# SCH_Szachy-schemat_2025-07-13.net
KiCad netlist of a schematic drawn in EasyEDA
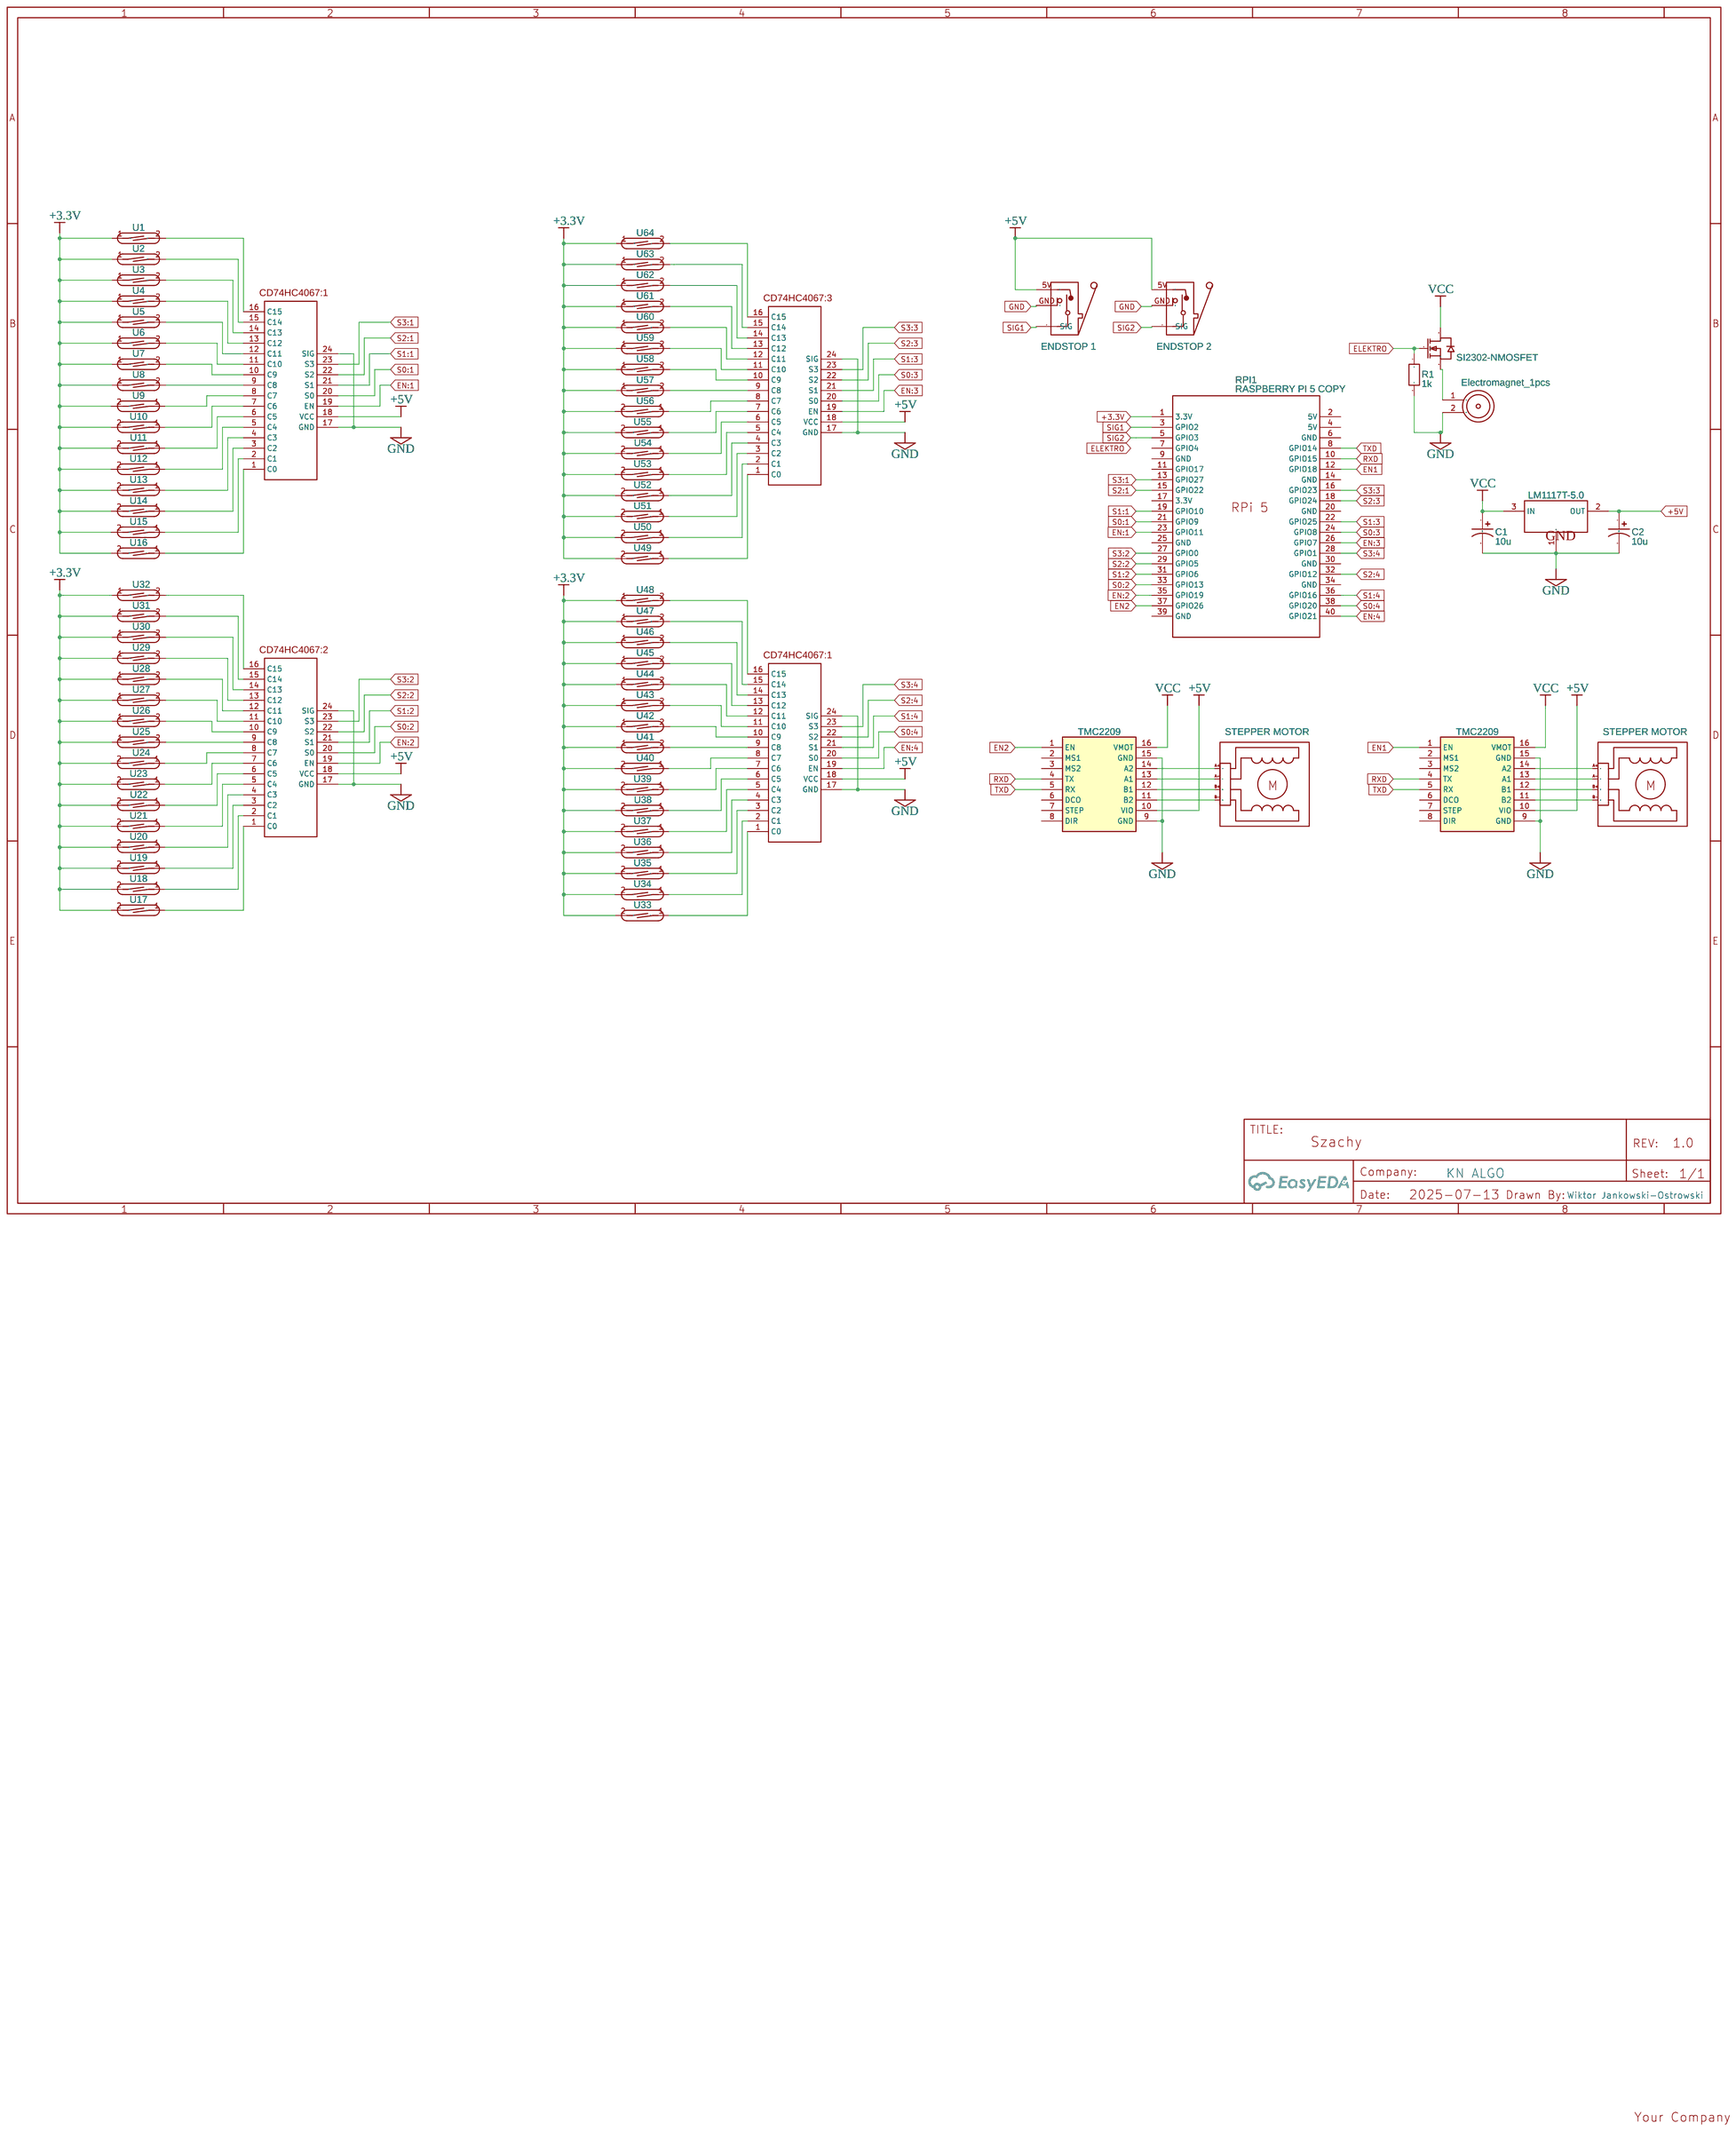
[diagram p0: schematic sheet]

(export (version "E")
  (design (tool "Eeschema 10.0.6"))
  (components
    (comp (ref "C1") (value "10u") (libsource (lib "") (part "C_Tan_SMD_A_US")))
    (comp (ref "C2") (value "10u") (libsource (lib "") (part "C_Tan_SMD_A_US")))
    (comp (ref "ESTP_FU1") (value "ENDSTOP 1") (libsource (lib "") (part "EndStop")))
    (comp (ref "ESTP_FU2") (value "ENDSTOP 2") (libsource (lib "") (part "EndStop")))
    (comp (ref "P1") (value "CD74HC4067SOLOV") (libsource (lib "") (part "CD74HC4067SOLOV")))
    (comp (ref "P2") (value "CD74HC4067SOLOV") (libsource (lib "") (part "CD74HC4067SOLOV_2")))
    (comp (ref "P3") (value "CD74HC4067SOLOV") (libsource (lib "") (part "CD74HC4067SOLOV")))
    (comp (ref "P4") (value "CD74HC4067SOLOV") (libsource (lib "") (part "CD74HC4067SOLOV_1")))
    (comp (ref "P5")
      (value "STEPPER MOTOR")
      (fields
        (field (name "Manufacturer Part") "Header-Male-2.54_1x6")
        (field (name "Manufacturer") "BOOMELE")
      )
      (libsource (lib "") (part "STEPPER MOTOR AM34HD1404-06 COPY"))
    )
    (comp (ref "P6")
      (value "STEPPER MOTOR")
      (fields
        (field (name "Manufacturer Part") "Header-Male-2.54_1x6")
        (field (name "Manufacturer") "BOOMELE")
      )
      (libsource (lib "") (part "STEPPER MOTOR AM34HD1404-06 COPY"))
    )
    (comp (ref "R1") (value "1k") (libsource (lib "") (part "R_0603_EU")))
    (comp (ref "RPI1")
      (value "RASPBERRY PI 5 COPY")
      (fields (field (name "Manufacturer") "Raspberry Pi 5 4GB"))
      (libsource (lib "") (part "RASPBERRY PI 5 COPY"))
    )
    (comp (ref "U1") (value "REED_SWITCH_D-C37") (libsource (lib "") (part "REED_SWITCH_D-C37")))
    (comp (ref "U2") (value "REED_SWITCH_D-C37") (libsource (lib "") (part "REED_SWITCH_D-C37")))
    (comp (ref "U3") (value "REED_SWITCH_D-C37") (libsource (lib "") (part "REED_SWITCH_D-C37")))
    (comp (ref "U4") (value "REED_SWITCH_D-C37") (libsource (lib "") (part "REED_SWITCH_D-C37")))
    (comp (ref "U5") (value "REED_SWITCH_D-C37") (libsource (lib "") (part "REED_SWITCH_D-C37")))
    (comp (ref "U6") (value "REED_SWITCH_D-C37") (libsource (lib "") (part "REED_SWITCH_D-C37")))
    (comp (ref "U7") (value "REED_SWITCH_D-C37") (libsource (lib "") (part "REED_SWITCH_D-C37")))
    (comp (ref "U8") (value "REED_SWITCH_D-C37") (libsource (lib "") (part "REED_SWITCH_D-C37")))
    (comp (ref "U9") (value "REED_SWITCH_D-C37") (libsource (lib "") (part "REED_SWITCH_D-C37_1")))
    (comp (ref "U10") (value "REED_SWITCH_D-C37") (libsource (lib "") (part "REED_SWITCH_D-C37_1")))
    (comp (ref "U11") (value "REED_SWITCH_D-C37") (libsource (lib "") (part "REED_SWITCH_D-C37_1")))
    (comp (ref "U12") (value "REED_SWITCH_D-C37") (libsource (lib "") (part "REED_SWITCH_D-C37_1")))
    (comp (ref "U13") (value "REED_SWITCH_D-C37") (libsource (lib "") (part "REED_SWITCH_D-C37_1")))
    (comp (ref "U14") (value "REED_SWITCH_D-C37") (libsource (lib "") (part "REED_SWITCH_D-C37_1")))
    (comp (ref "U15") (value "REED_SWITCH_D-C37") (libsource (lib "") (part "REED_SWITCH_D-C37_1")))
    (comp (ref "U16") (value "REED_SWITCH_D-C37") (libsource (lib "") (part "REED_SWITCH_D-C37_1")))
    (comp (ref "U17") (value "REED_SWITCH_D-C37") (libsource (lib "") (part "REED_SWITCH_D-C37_1")))
    (comp (ref "U18") (value "REED_SWITCH_D-C37") (libsource (lib "") (part "REED_SWITCH_D-C37_1")))
    (comp (ref "U19") (value "REED_SWITCH_D-C37") (libsource (lib "") (part "REED_SWITCH_D-C37_1")))
    (comp (ref "U20") (value "REED_SWITCH_D-C37") (libsource (lib "") (part "REED_SWITCH_D-C37_1")))
    (comp (ref "U21") (value "REED_SWITCH_D-C37") (libsource (lib "") (part "REED_SWITCH_D-C37_1")))
    (comp (ref "U22") (value "REED_SWITCH_D-C37") (libsource (lib "") (part "REED_SWITCH_D-C37_1")))
    (comp (ref "U23") (value "REED_SWITCH_D-C37") (libsource (lib "") (part "REED_SWITCH_D-C37_1")))
    (comp (ref "U24") (value "REED_SWITCH_D-C37") (libsource (lib "") (part "REED_SWITCH_D-C37_1")))
    (comp (ref "U25") (value "REED_SWITCH_D-C37") (libsource (lib "") (part "REED_SWITCH_D-C37")))
    (comp (ref "U26") (value "REED_SWITCH_D-C37") (libsource (lib "") (part "REED_SWITCH_D-C37")))
    (comp (ref "U27") (value "REED_SWITCH_D-C37") (libsource (lib "") (part "REED_SWITCH_D-C37")))
    (comp (ref "U28") (value "REED_SWITCH_D-C37") (libsource (lib "") (part "REED_SWITCH_D-C37")))
    (comp (ref "U29") (value "REED_SWITCH_D-C37") (libsource (lib "") (part "REED_SWITCH_D-C37")))
    (comp (ref "U30") (value "REED_SWITCH_D-C37") (libsource (lib "") (part "REED_SWITCH_D-C37")))
    (comp (ref "U31") (value "REED_SWITCH_D-C37") (libsource (lib "") (part "REED_SWITCH_D-C37")))
    (comp (ref "U32") (value "REED_SWITCH_D-C37") (libsource (lib "") (part "REED_SWITCH_D-C37")))
    (comp (ref "U33") (value "REED_SWITCH_D-C37") (libsource (lib "") (part "REED_SWITCH_D-C37_1")))
    (comp (ref "U34") (value "REED_SWITCH_D-C37") (libsource (lib "") (part "REED_SWITCH_D-C37_1")))
    (comp (ref "U35") (value "REED_SWITCH_D-C37") (libsource (lib "") (part "REED_SWITCH_D-C37_1")))
    (comp (ref "U36") (value "REED_SWITCH_D-C37") (libsource (lib "") (part "REED_SWITCH_D-C37_1")))
    (comp (ref "U37") (value "REED_SWITCH_D-C37") (libsource (lib "") (part "REED_SWITCH_D-C37_1")))
    (comp (ref "U38") (value "REED_SWITCH_D-C37") (libsource (lib "") (part "REED_SWITCH_D-C37_1")))
    (comp (ref "U39") (value "REED_SWITCH_D-C37") (libsource (lib "") (part "REED_SWITCH_D-C37_1")))
    (comp (ref "U40") (value "REED_SWITCH_D-C37") (libsource (lib "") (part "REED_SWITCH_D-C37_1")))
    (comp (ref "U41") (value "REED_SWITCH_D-C37") (libsource (lib "") (part "REED_SWITCH_D-C37")))
    (comp (ref "U42") (value "REED_SWITCH_D-C37") (libsource (lib "") (part "REED_SWITCH_D-C37")))
    (comp (ref "U43") (value "REED_SWITCH_D-C37") (libsource (lib "") (part "REED_SWITCH_D-C37")))
    (comp (ref "U44") (value "REED_SWITCH_D-C37") (libsource (lib "") (part "REED_SWITCH_D-C37")))
    (comp (ref "U45") (value "REED_SWITCH_D-C37") (libsource (lib "") (part "REED_SWITCH_D-C37")))
    (comp (ref "U46") (value "REED_SWITCH_D-C37") (libsource (lib "") (part "REED_SWITCH_D-C37")))
    (comp (ref "U47") (value "REED_SWITCH_D-C37") (libsource (lib "") (part "REED_SWITCH_D-C37")))
    (comp (ref "U48") (value "REED_SWITCH_D-C37") (libsource (lib "") (part "REED_SWITCH_D-C37")))
    (comp (ref "U49") (value "REED_SWITCH_D-C37") (libsource (lib "") (part "REED_SWITCH_D-C37_1")))
    (comp (ref "U50") (value "REED_SWITCH_D-C37") (libsource (lib "") (part "REED_SWITCH_D-C37_1")))
    (comp (ref "U51") (value "REED_SWITCH_D-C37") (libsource (lib "") (part "REED_SWITCH_D-C37_1")))
    (comp (ref "U52") (value "REED_SWITCH_D-C37") (libsource (lib "") (part "REED_SWITCH_D-C37_1")))
    (comp (ref "U53") (value "REED_SWITCH_D-C37") (libsource (lib "") (part "REED_SWITCH_D-C37_1")))
    (comp (ref "U54") (value "REED_SWITCH_D-C37") (libsource (lib "") (part "REED_SWITCH_D-C37_1")))
    (comp (ref "U55") (value "REED_SWITCH_D-C37") (libsource (lib "") (part "REED_SWITCH_D-C37_1")))
    (comp (ref "U56") (value "REED_SWITCH_D-C37") (libsource (lib "") (part "REED_SWITCH_D-C37_1")))
    (comp (ref "U57") (value "REED_SWITCH_D-C37") (libsource (lib "") (part "REED_SWITCH_D-C37")))
    (comp (ref "U58") (value "REED_SWITCH_D-C37") (libsource (lib "") (part "REED_SWITCH_D-C37")))
    (comp (ref "U59") (value "REED_SWITCH_D-C37") (libsource (lib "") (part "REED_SWITCH_D-C37")))
    (comp (ref "U60") (value "REED_SWITCH_D-C37") (libsource (lib "") (part "REED_SWITCH_D-C37")))
    (comp (ref "U61") (value "REED_SWITCH_D-C37") (libsource (lib "") (part "REED_SWITCH_D-C37")))
    (comp (ref "U62") (value "REED_SWITCH_D-C37") (libsource (lib "") (part "REED_SWITCH_D-C37")))
    (comp (ref "U63") (value "REED_SWITCH_D-C37") (libsource (lib "") (part "REED_SWITCH_D-C37")))
    (comp (ref "U64") (value "REED_SWITCH_D-C37") (libsource (lib "") (part "REED_SWITCH_D-C37")))
    (comp (ref "U65") (value "LM1117T-5.0") (libsource (lib "") (part "LM1117T-5.0")))
    (comp (ref "U66") (value "TMC2209") (libsource (lib "") (part "TMC2209")))
    (comp (ref "U67") (value "TMC2209") (libsource (lib "") (part "TMC2209")))
    (comp (ref "U68")
      (value "SI2302-NMOSFET")
      (fields (field (name "Manufacturer Part") "si2302-nmosfet"))
      (libsource (lib "") (part "SI2302-NMOSFET"))
    )
    (comp (ref "U69") (value "Electromagnet_1pcs") (libsource (lib "") (part "Electromagnet_1pcs")))
  )
  (nets
    (net (code "1") (name "+3.3V") (class "Default")
      (node (ref "RPI1") (pin "1") (pinfunction "3.3V_1") (pintype "passive"))
      (node (ref "U1") (pin "1") (pinfunction "1_1") (pintype "unspecified"))
      (node (ref "U10") (pin "2") (pinfunction "2_2") (pintype "unspecified"))
      (node (ref "U11") (pin "2") (pinfunction "2_2") (pintype "unspecified"))
      (node (ref "U12") (pin "2") (pinfunction "2_2") (pintype "unspecified"))
      (node (ref "U13") (pin "2") (pinfunction "2_2") (pintype "unspecified"))
      (node (ref "U14") (pin "2") (pinfunction "2_2") (pintype "unspecified"))
      (node (ref "U15") (pin "2") (pinfunction "2_2") (pintype "unspecified"))
      (node (ref "U16") (pin "2") (pinfunction "2_2") (pintype "unspecified"))
      (node (ref "U17") (pin "2") (pinfunction "2_2") (pintype "unspecified"))
      (node (ref "U18") (pin "2") (pinfunction "2_2") (pintype "unspecified"))
      (node (ref "U19") (pin "2") (pinfunction "2_2") (pintype "unspecified"))
      (node (ref "U2") (pin "1") (pinfunction "1_1") (pintype "unspecified"))
      (node (ref "U20") (pin "2") (pinfunction "2_2") (pintype "unspecified"))
      (node (ref "U21") (pin "2") (pinfunction "2_2") (pintype "unspecified"))
      (node (ref "U22") (pin "2") (pinfunction "2_2") (pintype "unspecified"))
      (node (ref "U23") (pin "2") (pinfunction "2_2") (pintype "unspecified"))
      (node (ref "U24") (pin "2") (pinfunction "2_2") (pintype "unspecified"))
      (node (ref "U25") (pin "1") (pinfunction "1_1") (pintype "unspecified"))
      (node (ref "U26") (pin "1") (pinfunction "1_1") (pintype "unspecified"))
      (node (ref "U27") (pin "1") (pinfunction "1_1") (pintype "unspecified"))
      (node (ref "U28") (pin "1") (pinfunction "1_1") (pintype "unspecified"))
      (node (ref "U29") (pin "1") (pinfunction "1_1") (pintype "unspecified"))
      (node (ref "U3") (pin "1") (pinfunction "1_1") (pintype "unspecified"))
      (node (ref "U30") (pin "1") (pinfunction "1_1") (pintype "unspecified"))
      (node (ref "U31") (pin "1") (pinfunction "1_1") (pintype "unspecified"))
      (node (ref "U32") (pin "1") (pinfunction "1_1") (pintype "unspecified"))
      (node (ref "U33") (pin "2") (pinfunction "2_2") (pintype "unspecified"))
      (node (ref "U34") (pin "2") (pinfunction "2_2") (pintype "unspecified"))
      (node (ref "U35") (pin "2") (pinfunction "2_2") (pintype "unspecified"))
      (node (ref "U36") (pin "2") (pinfunction "2_2") (pintype "unspecified"))
      (node (ref "U37") (pin "2") (pinfunction "2_2") (pintype "unspecified"))
      (node (ref "U38") (pin "2") (pinfunction "2_2") (pintype "unspecified"))
      (node (ref "U39") (pin "2") (pinfunction "2_2") (pintype "unspecified"))
      (node (ref "U4") (pin "1") (pinfunction "1_1") (pintype "unspecified"))
      (node (ref "U40") (pin "2") (pinfunction "2_2") (pintype "unspecified"))
      (node (ref "U41") (pin "1") (pinfunction "1_1") (pintype "unspecified"))
      (node (ref "U42") (pin "1") (pinfunction "1_1") (pintype "unspecified"))
      (node (ref "U43") (pin "1") (pinfunction "1_1") (pintype "unspecified"))
      (node (ref "U44") (pin "1") (pinfunction "1_1") (pintype "unspecified"))
      (node (ref "U45") (pin "1") (pinfunction "1_1") (pintype "unspecified"))
      (node (ref "U46") (pin "1") (pinfunction "1_1") (pintype "unspecified"))
      (node (ref "U47") (pin "1") (pinfunction "1_1") (pintype "unspecified"))
      (node (ref "U48") (pin "1") (pinfunction "1_1") (pintype "unspecified"))
      (node (ref "U49") (pin "2") (pinfunction "2_2") (pintype "unspecified"))
      (node (ref "U5") (pin "1") (pinfunction "1_1") (pintype "unspecified"))
      (node (ref "U50") (pin "2") (pinfunction "2_2") (pintype "unspecified"))
      (node (ref "U51") (pin "2") (pinfunction "2_2") (pintype "unspecified"))
      (node (ref "U52") (pin "2") (pinfunction "2_2") (pintype "unspecified"))
      (node (ref "U53") (pin "2") (pinfunction "2_2") (pintype "unspecified"))
      (node (ref "U54") (pin "2") (pinfunction "2_2") (pintype "unspecified"))
      (node (ref "U55") (pin "2") (pinfunction "2_2") (pintype "unspecified"))
      (node (ref "U56") (pin "2") (pinfunction "2_2") (pintype "unspecified"))
      (node (ref "U57") (pin "1") (pinfunction "1_1") (pintype "unspecified"))
      (node (ref "U58") (pin "1") (pinfunction "1_1") (pintype "unspecified"))
      (node (ref "U59") (pin "1") (pinfunction "1_1") (pintype "unspecified"))
      (node (ref "U6") (pin "1") (pinfunction "1_1") (pintype "unspecified"))
      (node (ref "U60") (pin "1") (pinfunction "1_1") (pintype "unspecified"))
      (node (ref "U61") (pin "1") (pinfunction "1_1") (pintype "unspecified"))
      (node (ref "U62") (pin "1") (pinfunction "1_1") (pintype "unspecified"))
      (node (ref "U63") (pin "1") (pinfunction "1_1") (pintype "unspecified"))
      (node (ref "U64") (pin "1") (pinfunction "1_1") (pintype "unspecified"))
      (node (ref "U7") (pin "1") (pinfunction "1_1") (pintype "unspecified"))
      (node (ref "U8") (pin "1") (pinfunction "1_1") (pintype "unspecified"))
      (node (ref "U9") (pin "2") (pinfunction "2_2") (pintype "unspecified"))
    )
    (net (code "2") (name "+5V") (class "Default")
      (node (ref "C2") (pin "1") (pinfunction "1_1") (pintype "unspecified"))
      (node (ref "ESTP_FU1") (pin "5V") (pinfunction "2_5V") (pintype "unspecified"))
      (node (ref "ESTP_FU2") (pin "5V") (pinfunction "2_5V") (pintype "unspecified"))
      (node (ref "P1") (pin "18") (pinfunction "VCC_18") (pintype "unspecified"))
      (node (ref "P2") (pin "18") (pinfunction "VCC_18") (pintype "unspecified"))
      (node (ref "P3") (pin "18") (pinfunction "VCC_18") (pintype "unspecified"))
      (node (ref "P4") (pin "18") (pinfunction "VCC_18") (pintype "unspecified"))
      (node (ref "U65") (pin "2") (pinfunction "OUT_2") (pintype "passive"))
      (node (ref "U66") (pin "10") (pinfunction "VIO_10") (pintype "unspecified"))
      (node (ref "U67") (pin "10") (pinfunction "VIO_10") (pintype "unspecified"))
    )
    (net (code "3") (name "ELEKTRO") (class "Default")
      (node (ref "R1") (pin "1") (pinfunction "1_1") (pintype "unspecified"))
      (node (ref "U68") (pin "1") (pinfunction "G_1") (pintype "unspecified"))
    )
    (net (code "4") (name "EN1") (class "Default")
      (node (ref "RPI1") (pin "12") (pinfunction "GPIO18_12") (pintype "bidirectional"))
      (node (ref "U67") (pin "1") (pinfunction "EN_1") (pintype "unspecified"))
    )
    (net (code "5") (name "EN2") (class "Default")
      (node (ref "RPI1") (pin "37") (pinfunction "GPIO26_37") (pintype "bidirectional"))
      (node (ref "U66") (pin "1") (pinfunction "EN_1") (pintype "unspecified"))
    )
    (net (code "6") (name "EN:1") (class "Default")
      (node (ref "P1") (pin "19") (pinfunction "EN_19") (pintype "unspecified"))
      (node (ref "RPI1") (pin "23") (pinfunction "GPIO11_23") (pintype "bidirectional"))
    )
    (net (code "7") (name "EN:2") (class "Default")
      (node (ref "P2") (pin "19") (pinfunction "EN_19") (pintype "unspecified"))
      (node (ref "RPI1") (pin "35") (pinfunction "GPIO19_35") (pintype "bidirectional"))
    )
    (net (code "8") (name "EN:3") (class "Default")
      (node (ref "P4") (pin "19") (pinfunction "EN_19") (pintype "unspecified"))
      (node (ref "RPI1") (pin "26") (pinfunction "GPIO7_26") (pintype "bidirectional"))
    )
    (net (code "9") (name "EN:4") (class "Default")
      (node (ref "P3") (pin "19") (pinfunction "EN_19") (pintype "unspecified"))
      (node (ref "RPI1") (pin "40") (pinfunction "GPIO21_40") (pintype "bidirectional"))
    )
    (net (code "10") (name "GND") (class "Default")
      (node (ref "C1") (pin "2") (pinfunction "2_2") (pintype "unspecified"))
      (node (ref "C2") (pin "2") (pinfunction "2_2") (pintype "unspecified"))
      (node (ref "ESTP_FU1") (pin "GND") (pinfunction "3_GND") (pintype "unspecified"))
      (node (ref "ESTP_FU2") (pin "GND") (pinfunction "3_GND") (pintype "unspecified"))
      (node (ref "P1") (pin "17") (pinfunction "GND_17") (pintype "unspecified"))
      (node (ref "P1") (pin "24") (pinfunction "SIG_24") (pintype "unspecified"))
      (node (ref "P2") (pin "17") (pinfunction "GND_17") (pintype "unspecified"))
      (node (ref "P2") (pin "24") (pinfunction "SIG_24") (pintype "unspecified"))
      (node (ref "P3") (pin "17") (pinfunction "GND_17") (pintype "unspecified"))
      (node (ref "P3") (pin "24") (pinfunction "SIG_24") (pintype "unspecified"))
      (node (ref "P4") (pin "17") (pinfunction "GND_17") (pintype "unspecified"))
      (node (ref "P4") (pin "24") (pinfunction "SIG_24") (pintype "unspecified"))
      (node (ref "R1") (pin "2") (pinfunction "2_2") (pintype "unspecified"))
      (node (ref "U65") (pin "1") (pinfunction "GND_1") (pintype "passive"))
      (node (ref "U66") (pin "15") (pinfunction "GND_15") (pintype "unspecified"))
      (node (ref "U66") (pin "9") (pinfunction "GND_9") (pintype "unspecified"))
      (node (ref "U67") (pin "15") (pinfunction "GND_15") (pintype "unspecified"))
      (node (ref "U67") (pin "9") (pinfunction "GND_9") (pintype "unspecified"))
      (node (ref "U69") (pin "2") (pinfunction "2_2") (pintype "unspecified"))
    )
    (net (code "11") (name "Net-(P1-C0)") (class "Default")
      (node (ref "P1") (pin "1") (pinfunction "C0_1") (pintype "unspecified"))
      (node (ref "U16") (pin "1") (pinfunction "1_1") (pintype "unspecified"))
    )
    (net (code "12") (name "Net-(P1-C1)") (class "Default")
      (node (ref "P1") (pin "2") (pinfunction "C1_2") (pintype "unspecified"))
      (node (ref "U15") (pin "1") (pinfunction "1_1") (pintype "unspecified"))
    )
    (net (code "13") (name "Net-(P1-C2)") (class "Default")
      (node (ref "P1") (pin "3") (pinfunction "C2_3") (pintype "unspecified"))
      (node (ref "U14") (pin "1") (pinfunction "1_1") (pintype "unspecified"))
    )
    (net (code "14") (name "Net-(P1-C3)") (class "Default")
      (node (ref "P1") (pin "4") (pinfunction "C3_4") (pintype "unspecified"))
      (node (ref "U13") (pin "1") (pinfunction "1_1") (pintype "unspecified"))
    )
    (net (code "15") (name "Net-(P1-C4)") (class "Default")
      (node (ref "P1") (pin "5") (pinfunction "C4_5") (pintype "unspecified"))
      (node (ref "U12") (pin "1") (pinfunction "1_1") (pintype "unspecified"))
    )
    (net (code "16") (name "Net-(P1-C5)") (class "Default")
      (node (ref "P1") (pin "6") (pinfunction "C5_6") (pintype "unspecified"))
      (node (ref "U11") (pin "1") (pinfunction "1_1") (pintype "unspecified"))
    )
    (net (code "17") (name "Net-(P1-C6)") (class "Default")
      (node (ref "P1") (pin "7") (pinfunction "C6_7") (pintype "unspecified"))
      (node (ref "U10") (pin "1") (pinfunction "1_1") (pintype "unspecified"))
    )
    (net (code "18") (name "Net-(P1-C7)") (class "Default")
      (node (ref "P1") (pin "8") (pinfunction "C7_8") (pintype "unspecified"))
      (node (ref "U9") (pin "1") (pinfunction "1_1") (pintype "unspecified"))
    )
    (net (code "19") (name "Net-(P1-C8)") (class "Default")
      (node (ref "P1") (pin "9") (pinfunction "C8_9") (pintype "unspecified"))
      (node (ref "U8") (pin "2") (pinfunction "2_2") (pintype "unspecified"))
    )
    (net (code "20") (name "Net-(P1-C9)") (class "Default")
      (node (ref "P1") (pin "10") (pinfunction "C9_10") (pintype "unspecified"))
      (node (ref "U7") (pin "2") (pinfunction "2_2") (pintype "unspecified"))
    )
    (net (code "21") (name "Net-(P1-C10)") (class "Default")
      (node (ref "P1") (pin "11") (pinfunction "C10_11") (pintype "unspecified"))
      (node (ref "U6") (pin "2") (pinfunction "2_2") (pintype "unspecified"))
    )
    (net (code "22") (name "Net-(P1-C11)") (class "Default")
      (node (ref "P1") (pin "12") (pinfunction "C11_12") (pintype "unspecified"))
      (node (ref "U5") (pin "2") (pinfunction "2_2") (pintype "unspecified"))
    )
    (net (code "23") (name "Net-(P1-C12)") (class "Default")
      (node (ref "P1") (pin "13") (pinfunction "C12_13") (pintype "unspecified"))
      (node (ref "U4") (pin "2") (pinfunction "2_2") (pintype "unspecified"))
    )
    (net (code "24") (name "Net-(P1-C13)") (class "Default")
      (node (ref "P1") (pin "14") (pinfunction "C13_14") (pintype "unspecified"))
      (node (ref "U3") (pin "2") (pinfunction "2_2") (pintype "unspecified"))
    )
    (net (code "25") (name "Net-(P1-C14)") (class "Default")
      (node (ref "P1") (pin "15") (pinfunction "C14_15") (pintype "unspecified"))
      (node (ref "U2") (pin "2") (pinfunction "2_2") (pintype "unspecified"))
    )
    (net (code "26") (name "Net-(P1-C15)") (class "Default")
      (node (ref "P1") (pin "16") (pinfunction "C15_16") (pintype "unspecified"))
      (node (ref "U1") (pin "2") (pinfunction "2_2") (pintype "unspecified"))
    )
    (net (code "27") (name "Net-(P2-C0)") (class "Default")
      (node (ref "P2") (pin "1") (pinfunction "C0_1") (pintype "unspecified"))
      (node (ref "U17") (pin "1") (pinfunction "1_1") (pintype "unspecified"))
    )
    (net (code "28") (name "Net-(P2-C1)") (class "Default")
      (node (ref "P2") (pin "2") (pinfunction "C1_2") (pintype "unspecified"))
      (node (ref "U18") (pin "1") (pinfunction "1_1") (pintype "unspecified"))
    )
    (net (code "29") (name "Net-(P2-C2)") (class "Default")
      (node (ref "P2") (pin "3") (pinfunction "C2_3") (pintype "unspecified"))
      (node (ref "U19") (pin "1") (pinfunction "1_1") (pintype "unspecified"))
    )
    (net (code "30") (name "Net-(P2-C3)") (class "Default")
      (node (ref "P2") (pin "4") (pinfunction "C3_4") (pintype "unspecified"))
      (node (ref "U20") (pin "1") (pinfunction "1_1") (pintype "unspecified"))
    )
    (net (code "31") (name "Net-(P2-C4)") (class "Default")
      (node (ref "P2") (pin "5") (pinfunction "C4_5") (pintype "unspecified"))
      (node (ref "U21") (pin "1") (pinfunction "1_1") (pintype "unspecified"))
    )
    (net (code "32") (name "Net-(P2-C5)") (class "Default")
      (node (ref "P2") (pin "6") (pinfunction "C5_6") (pintype "unspecified"))
      (node (ref "U22") (pin "1") (pinfunction "1_1") (pintype "unspecified"))
    )
    (net (code "33") (name "Net-(P2-C6)") (class "Default")
      (node (ref "P2") (pin "7") (pinfunction "C6_7") (pintype "unspecified"))
      (node (ref "U23") (pin "1") (pinfunction "1_1") (pintype "unspecified"))
    )
    (net (code "34") (name "Net-(P2-C7)") (class "Default")
      (node (ref "P2") (pin "8") (pinfunction "C7_8") (pintype "unspecified"))
      (node (ref "U24") (pin "1") (pinfunction "1_1") (pintype "unspecified"))
    )
    (net (code "35") (name "Net-(P2-C8)") (class "Default")
      (node (ref "P2") (pin "9") (pinfunction "C8_9") (pintype "unspecified"))
      (node (ref "U25") (pin "2") (pinfunction "2_2") (pintype "unspecified"))
    )
    (net (code "36") (name "Net-(P2-C9)") (class "Default")
      (node (ref "P2") (pin "10") (pinfunction "C9_10") (pintype "unspecified"))
      (node (ref "U26") (pin "2") (pinfunction "2_2") (pintype "unspecified"))
    )
    (net (code "37") (name "Net-(P2-C10)") (class "Default")
      (node (ref "P2") (pin "11") (pinfunction "C10_11") (pintype "unspecified"))
      (node (ref "U27") (pin "2") (pinfunction "2_2") (pintype "unspecified"))
    )
    (net (code "38") (name "Net-(P2-C11)") (class "Default")
      (node (ref "P2") (pin "12") (pinfunction "C11_12") (pintype "unspecified"))
      (node (ref "U28") (pin "2") (pinfunction "2_2") (pintype "unspecified"))
    )
    (net (code "39") (name "Net-(P2-C12)") (class "Default")
      (node (ref "P2") (pin "13") (pinfunction "C12_13") (pintype "unspecified"))
      (node (ref "U29") (pin "2") (pinfunction "2_2") (pintype "unspecified"))
    )
    (net (code "40") (name "Net-(P2-C13)") (class "Default")
      (node (ref "P2") (pin "14") (pinfunction "C13_14") (pintype "unspecified"))
      (node (ref "U30") (pin "2") (pinfunction "2_2") (pintype "unspecified"))
    )
    (net (code "41") (name "Net-(P2-C14)") (class "Default")
      (node (ref "P2") (pin "15") (pinfunction "C14_15") (pintype "unspecified"))
      (node (ref "U31") (pin "2") (pinfunction "2_2") (pintype "unspecified"))
    )
    (net (code "42") (name "Net-(P2-C15)") (class "Default")
      (node (ref "P2") (pin "16") (pinfunction "C15_16") (pintype "unspecified"))
      (node (ref "U32") (pin "2") (pinfunction "2_2") (pintype "unspecified"))
    )
    (net (code "43") (name "Net-(P3-C0)") (class "Default")
      (node (ref "P3") (pin "1") (pinfunction "C0_1") (pintype "unspecified"))
      (node (ref "U33") (pin "1") (pinfunction "1_1") (pintype "unspecified"))
    )
    (net (code "44") (name "Net-(P3-C1)") (class "Default")
      (node (ref "P3") (pin "2") (pinfunction "C1_2") (pintype "unspecified"))
      (node (ref "U34") (pin "1") (pinfunction "1_1") (pintype "unspecified"))
    )
    (net (code "45") (name "Net-(P3-C2)") (class "Default")
      (node (ref "P3") (pin "3") (pinfunction "C2_3") (pintype "unspecified"))
      (node (ref "U35") (pin "1") (pinfunction "1_1") (pintype "unspecified"))
    )
    (net (code "46") (name "Net-(P3-C3)") (class "Default")
      (node (ref "P3") (pin "4") (pinfunction "C3_4") (pintype "unspecified"))
      (node (ref "U36") (pin "1") (pinfunction "1_1") (pintype "unspecified"))
    )
    (net (code "47") (name "Net-(P3-C4)") (class "Default")
      (node (ref "P3") (pin "5") (pinfunction "C4_5") (pintype "unspecified"))
      (node (ref "U37") (pin "1") (pinfunction "1_1") (pintype "unspecified"))
    )
    (net (code "48") (name "Net-(P3-C5)") (class "Default")
      (node (ref "P3") (pin "6") (pinfunction "C5_6") (pintype "unspecified"))
      (node (ref "U38") (pin "1") (pinfunction "1_1") (pintype "unspecified"))
    )
    (net (code "49") (name "Net-(P3-C6)") (class "Default")
      (node (ref "P3") (pin "7") (pinfunction "C6_7") (pintype "unspecified"))
      (node (ref "U39") (pin "1") (pinfunction "1_1") (pintype "unspecified"))
    )
    (net (code "50") (name "Net-(P3-C7)") (class "Default")
      (node (ref "P3") (pin "8") (pinfunction "C7_8") (pintype "unspecified"))
      (node (ref "U40") (pin "1") (pinfunction "1_1") (pintype "unspecified"))
    )
    (net (code "51") (name "Net-(P3-C8)") (class "Default")
      (node (ref "P3") (pin "9") (pinfunction "C8_9") (pintype "unspecified"))
      (node (ref "U41") (pin "2") (pinfunction "2_2") (pintype "unspecified"))
    )
    (net (code "52") (name "Net-(P3-C9)") (class "Default")
      (node (ref "P3") (pin "10") (pinfunction "C9_10") (pintype "unspecified"))
      (node (ref "U42") (pin "2") (pinfunction "2_2") (pintype "unspecified"))
    )
    (net (code "53") (name "Net-(P3-C10)") (class "Default")
      (node (ref "P3") (pin "11") (pinfunction "C10_11") (pintype "unspecified"))
      (node (ref "U43") (pin "2") (pinfunction "2_2") (pintype "unspecified"))
    )
    (net (code "54") (name "Net-(P3-C11)") (class "Default")
      (node (ref "P3") (pin "12") (pinfunction "C11_12") (pintype "unspecified"))
      (node (ref "U44") (pin "2") (pinfunction "2_2") (pintype "unspecified"))
    )
    (net (code "55") (name "Net-(P3-C12)") (class "Default")
      (node (ref "P3") (pin "13") (pinfunction "C12_13") (pintype "unspecified"))
      (node (ref "U45") (pin "2") (pinfunction "2_2") (pintype "unspecified"))
    )
    (net (code "56") (name "Net-(P3-C13)") (class "Default")
      (node (ref "P3") (pin "14") (pinfunction "C13_14") (pintype "unspecified"))
      (node (ref "U46") (pin "2") (pinfunction "2_2") (pintype "unspecified"))
    )
    (net (code "57") (name "Net-(P3-C14)") (class "Default")
      (node (ref "P3") (pin "15") (pinfunction "C14_15") (pintype "unspecified"))
      (node (ref "U47") (pin "2") (pinfunction "2_2") (pintype "unspecified"))
    )
    (net (code "58") (name "Net-(P3-C15)") (class "Default")
      (node (ref "P3") (pin "16") (pinfunction "C15_16") (pintype "unspecified"))
      (node (ref "U48") (pin "2") (pinfunction "2_2") (pintype "unspecified"))
    )
    (net (code "59") (name "Net-(P4-C0)") (class "Default")
      (node (ref "P4") (pin "1") (pinfunction "C0_1") (pintype "unspecified"))
      (node (ref "U49") (pin "1") (pinfunction "1_1") (pintype "unspecified"))
    )
    (net (code "60") (name "Net-(P4-C1)") (class "Default")
      (node (ref "P4") (pin "2") (pinfunction "C1_2") (pintype "unspecified"))
      (node (ref "U50") (pin "1") (pinfunction "1_1") (pintype "unspecified"))
    )
    (net (code "61") (name "Net-(P4-C2)") (class "Default")
      (node (ref "P4") (pin "3") (pinfunction "C2_3") (pintype "unspecified"))
      (node (ref "U51") (pin "1") (pinfunction "1_1") (pintype "unspecified"))
    )
    (net (code "62") (name "Net-(P4-C3)") (class "Default")
      (node (ref "P4") (pin "4") (pinfunction "C3_4") (pintype "unspecified"))
      (node (ref "U52") (pin "1") (pinfunction "1_1") (pintype "unspecified"))
    )
    (net (code "63") (name "Net-(P4-C4)") (class "Default")
      (node (ref "P4") (pin "5") (pinfunction "C4_5") (pintype "unspecified"))
      (node (ref "U53") (pin "1") (pinfunction "1_1") (pintype "unspecified"))
    )
    (net (code "64") (name "Net-(P4-C5)") (class "Default")
      (node (ref "P4") (pin "6") (pinfunction "C5_6") (pintype "unspecified"))
      (node (ref "U54") (pin "1") (pinfunction "1_1") (pintype "unspecified"))
    )
    (net (code "65") (name "Net-(P4-C6)") (class "Default")
      (node (ref "P4") (pin "7") (pinfunction "C6_7") (pintype "unspecified"))
      (node (ref "U55") (pin "1") (pinfunction "1_1") (pintype "unspecified"))
    )
    (net (code "66") (name "Net-(P4-C7)") (class "Default")
      (node (ref "P4") (pin "8") (pinfunction "C7_8") (pintype "unspecified"))
      (node (ref "U56") (pin "1") (pinfunction "1_1") (pintype "unspecified"))
    )
    (net (code "67") (name "Net-(P4-C8)") (class "Default")
      (node (ref "P4") (pin "9") (pinfunction "C8_9") (pintype "unspecified"))
      (node (ref "U57") (pin "2") (pinfunction "2_2") (pintype "unspecified"))
    )
    (net (code "68") (name "Net-(P4-C9)") (class "Default")
      (node (ref "P4") (pin "10") (pinfunction "C9_10") (pintype "unspecified"))
      (node (ref "U58") (pin "2") (pinfunction "2_2") (pintype "unspecified"))
    )
    (net (code "69") (name "Net-(P4-C10)") (class "Default")
      (node (ref "P4") (pin "11") (pinfunction "C10_11") (pintype "unspecified"))
      (node (ref "U59") (pin "2") (pinfunction "2_2") (pintype "unspecified"))
    )
    (net (code "70") (name "Net-(P4-C11)") (class "Default")
      (node (ref "P4") (pin "12") (pinfunction "C11_12") (pintype "unspecified"))
      (node (ref "U60") (pin "2") (pinfunction "2_2") (pintype "unspecified"))
    )
    (net (code "71") (name "Net-(P4-C12)") (class "Default")
      (node (ref "P4") (pin "13") (pinfunction "C12_13") (pintype "unspecified"))
      (node (ref "U61") (pin "2") (pinfunction "2_2") (pintype "unspecified"))
    )
    (net (code "72") (name "Net-(P4-C13)") (class "Default")
      (node (ref "P4") (pin "14") (pinfunction "C13_14") (pintype "unspecified"))
      (node (ref "U62") (pin "2") (pinfunction "2_2") (pintype "unspecified"))
    )
    (net (code "73") (name "Net-(P4-C14)") (class "Default")
      (node (ref "P4") (pin "15") (pinfunction "C14_15") (pintype "unspecified"))
      (node (ref "U63") (pin "2") (pinfunction "2_2") (pintype "unspecified"))
    )
    (net (code "74") (name "Net-(P4-C15)") (class "Default")
      (node (ref "P4") (pin "16") (pinfunction "C15_16") (pintype "unspecified"))
      (node (ref "U64") (pin "2") (pinfunction "2_2") (pintype "unspecified"))
    )
    (net (code "75") (name "Net-(U66-A1)") (class "Default")
      (node (ref "P5") (pin "A-") (pinfunction "A-_A-") (pintype "unspecified"))
      (node (ref "U66") (pin "13") (pinfunction "A1_13") (pintype "unspecified"))
    )
    (net (code "76") (name "Net-(U66-A2)") (class "Default")
      (node (ref "P5") (pin "A+") (pinfunction "A+_A+") (pintype "unspecified"))
      (node (ref "U66") (pin "14") (pinfunction "A2_14") (pintype "unspecified"))
    )
    (net (code "77") (name "Net-(U66-B1)") (class "Default")
      (node (ref "P5") (pin "B+") (pinfunction "B+_B+") (pintype "unspecified"))
      (node (ref "U66") (pin "12") (pinfunction "B1_12") (pintype "unspecified"))
    )
    (net (code "78") (name "Net-(U66-B2)") (class "Default")
      (node (ref "P5") (pin "B-") (pinfunction "B-_B-") (pintype "unspecified"))
      (node (ref "U66") (pin "11") (pinfunction "B2_11") (pintype "unspecified"))
    )
    (net (code "79") (name "Net-(U67-A1)") (class "Default")
      (node (ref "P6") (pin "A-") (pinfunction "A-_A-") (pintype "unspecified"))
      (node (ref "U67") (pin "13") (pinfunction "A1_13") (pintype "unspecified"))
    )
    (net (code "80") (name "Net-(U67-A2)") (class "Default")
      (node (ref "P6") (pin "A+") (pinfunction "A+_A+") (pintype "unspecified"))
      (node (ref "U67") (pin "14") (pinfunction "A2_14") (pintype "unspecified"))
    )
    (net (code "81") (name "Net-(U67-B1)") (class "Default")
      (node (ref "P6") (pin "B+") (pinfunction "B+_B+") (pintype "unspecified"))
      (node (ref "U67") (pin "12") (pinfunction "B1_12") (pintype "unspecified"))
    )
    (net (code "82") (name "Net-(U67-B2)") (class "Default")
      (node (ref "P6") (pin "B-") (pinfunction "B-_B-") (pintype "unspecified"))
      (node (ref "U67") (pin "11") (pinfunction "B2_11") (pintype "unspecified"))
    )
    (net (code "83") (name "Net-(U68-S)") (class "Default")
      (node (ref "U68") (pin "2") (pinfunction "S_2") (pintype "unspecified"))
      (node (ref "U69") (pin "1") (pinfunction "1_1") (pintype "unspecified"))
    )
    (net (code "84") (name "RXD") (class "Default")
      (node (ref "RPI1") (pin "10") (pinfunction "GPIO15_10") (pintype "bidirectional"))
      (node (ref "U66") (pin "4") (pinfunction "TX_4") (pintype "unspecified"))
      (node (ref "U67") (pin "4") (pinfunction "TX_4") (pintype "unspecified"))
    )
    (net (code "85") (name "S0:1") (class "Default")
      (node (ref "P1") (pin "20") (pinfunction "S0_20") (pintype "unspecified"))
      (node (ref "RPI1") (pin "21") (pinfunction "GPIO9_21") (pintype "bidirectional"))
    )
    (net (code "86") (name "S0:2") (class "Default")
      (node (ref "P2") (pin "20") (pinfunction "S0_20") (pintype "unspecified"))
      (node (ref "RPI1") (pin "33") (pinfunction "GPIO13_33") (pintype "bidirectional"))
    )
    (net (code "87") (name "S0:3") (class "Default")
      (node (ref "P4") (pin "20") (pinfunction "S0_20") (pintype "unspecified"))
      (node (ref "RPI1") (pin "24") (pinfunction "GPIO8_24") (pintype "bidirectional"))
    )
    (net (code "88") (name "S0:4") (class "Default")
      (node (ref "P3") (pin "20") (pinfunction "S0_20") (pintype "unspecified"))
      (node (ref "RPI1") (pin "38") (pinfunction "GPIO20_38") (pintype "bidirectional"))
    )
    (net (code "89") (name "S1:1") (class "Default")
      (node (ref "P1") (pin "21") (pinfunction "S1_21") (pintype "unspecified"))
      (node (ref "RPI1") (pin "19") (pinfunction "GPIO10_19") (pintype "bidirectional"))
    )
    (net (code "90") (name "S1:2") (class "Default")
      (node (ref "P2") (pin "21") (pinfunction "S1_21") (pintype "unspecified"))
      (node (ref "RPI1") (pin "31") (pinfunction "GPIO6_31") (pintype "bidirectional"))
    )
    (net (code "91") (name "S1:3") (class "Default")
      (node (ref "P4") (pin "21") (pinfunction "S1_21") (pintype "unspecified"))
      (node (ref "RPI1") (pin "22") (pinfunction "GPIO25_22") (pintype "bidirectional"))
    )
    (net (code "92") (name "S1:4") (class "Default")
      (node (ref "P3") (pin "21") (pinfunction "S1_21") (pintype "unspecified"))
      (node (ref "RPI1") (pin "36") (pinfunction "GPIO16_36") (pintype "bidirectional"))
    )
    (net (code "93") (name "S2:1") (class "Default")
      (node (ref "P1") (pin "22") (pinfunction "S2_22") (pintype "unspecified"))
      (node (ref "RPI1") (pin "15") (pinfunction "GPIO22_15") (pintype "bidirectional"))
    )
    (net (code "94") (name "S2:2") (class "Default")
      (node (ref "P2") (pin "22") (pinfunction "S2_22") (pintype "unspecified"))
      (node (ref "RPI1") (pin "29") (pinfunction "GPIO5_29") (pintype "bidirectional"))
    )
    (net (code "95") (name "S2:3") (class "Default")
      (node (ref "P4") (pin "22") (pinfunction "S2_22") (pintype "unspecified"))
      (node (ref "RPI1") (pin "18") (pinfunction "GPIO24_18") (pintype "bidirectional"))
    )
    (net (code "96") (name "S2:4") (class "Default")
      (node (ref "P3") (pin "22") (pinfunction "S2_22") (pintype "unspecified"))
      (node (ref "RPI1") (pin "32") (pinfunction "GPIO12_32") (pintype "bidirectional"))
    )
    (net (code "97") (name "S3:1") (class "Default")
      (node (ref "P1") (pin "23") (pinfunction "S3_23") (pintype "unspecified"))
      (node (ref "RPI1") (pin "13") (pinfunction "GPIO27_13") (pintype "bidirectional"))
    )
    (net (code "98") (name "S3:2") (class "Default")
      (node (ref "P2") (pin "23") (pinfunction "S3_23") (pintype "unspecified"))
      (node (ref "RPI1") (pin "27") (pinfunction "GPIO0_27") (pintype "unspecified"))
    )
    (net (code "99") (name "S3:3") (class "Default")
      (node (ref "P4") (pin "23") (pinfunction "S3_23") (pintype "unspecified"))
      (node (ref "RPI1") (pin "16") (pinfunction "GPIO23_16") (pintype "bidirectional"))
    )
    (net (code "100") (name "S3:4") (class "Default")
      (node (ref "P3") (pin "23") (pinfunction "S3_23") (pintype "unspecified"))
      (node (ref "RPI1") (pin "28") (pinfunction "GPIO1_28") (pintype "unspecified"))
    )
    (net (code "101") (name "SIG1") (class "Default")
      (node (ref "ESTP_FU1") (pin "1") (pinfunction "SIG_1") (pintype "unspecified"))
      (node (ref "RPI1") (pin "3") (pinfunction "GPIO2_3") (pintype "bidirectional"))
    )
    (net (code "102") (name "SIG2") (class "Default")
      (node (ref "ESTP_FU2") (pin "1") (pinfunction "SIG_1") (pintype "unspecified"))
      (node (ref "RPI1") (pin "5") (pinfunction "GPIO3_5") (pintype "bidirectional"))
    )
    (net (code "103") (name "TXD") (class "Default")
      (node (ref "RPI1") (pin "8") (pinfunction "GPIO14_8") (pintype "bidirectional"))
      (node (ref "U66") (pin "5") (pinfunction "RX_5") (pintype "unspecified"))
      (node (ref "U67") (pin "5") (pinfunction "RX_5") (pintype "unspecified"))
    )
    (net (code "104") (name "VCC") (class "Default")
      (node (ref "C1") (pin "1") (pinfunction "1_1") (pintype "unspecified"))
      (node (ref "U65") (pin "3") (pinfunction "IN_3") (pintype "passive"))
      (node (ref "U66") (pin "16") (pinfunction "VMOT_16") (pintype "unspecified"))
      (node (ref "U67") (pin "16") (pinfunction "VMOT_16") (pintype "unspecified"))
      (node (ref "U68") (pin "3") (pinfunction "D_3") (pintype "unspecified"))
    )
    (net (code "105") (name "unconnected-(RPI1-3.3V-Pad17)") (class "Default")
      (node (ref "RPI1") (pin "17") (pinfunction "3.3V_17") (pintype "passive"))
    )
    (net (code "106") (name "unconnected-(RPI1-5V-Pad2)") (class "Default")
      (node (ref "RPI1") (pin "2") (pinfunction "5V_2") (pintype "passive"))
    )
    (net (code "107") (name "unconnected-(RPI1-5V-Pad4)") (class "Default")
      (node (ref "RPI1") (pin "4") (pinfunction "5V_4") (pintype "passive"))
    )
    (net (code "108") (name "unconnected-(RPI1-GND-Pad6)") (class "Default")
      (node (ref "RPI1") (pin "6") (pinfunction "GND_6") (pintype "unspecified"))
    )
    (net (code "109") (name "unconnected-(RPI1-GND-Pad9)") (class "Default")
      (node (ref "RPI1") (pin "9") (pinfunction "GND_9") (pintype "unspecified"))
    )
    (net (code "110") (name "unconnected-(RPI1-GND-Pad14)") (class "Default")
      (node (ref "RPI1") (pin "14") (pinfunction "GND_14") (pintype "unspecified"))
    )
    (net (code "111") (name "unconnected-(RPI1-GND-Pad20)") (class "Default")
      (node (ref "RPI1") (pin "20") (pinfunction "GND_20") (pintype "unspecified"))
    )
    (net (code "112") (name "unconnected-(RPI1-GND-Pad25)") (class "Default")
      (node (ref "RPI1") (pin "25") (pinfunction "GND_25") (pintype "unspecified"))
    )
    (net (code "113") (name "unconnected-(RPI1-GND-Pad30)") (class "Default")
      (node (ref "RPI1") (pin "30") (pinfunction "GND_30") (pintype "unspecified"))
    )
    (net (code "114") (name "unconnected-(RPI1-GND-Pad34)") (class "Default")
      (node (ref "RPI1") (pin "34") (pinfunction "GND_34") (pintype "unspecified"))
    )
    (net (code "115") (name "unconnected-(RPI1-GND-Pad39)") (class "Default")
      (node (ref "RPI1") (pin "39") (pinfunction "GND_39") (pintype "unspecified"))
    )
    (net (code "116") (name "unconnected-(RPI1-GPIO4-Pad7)") (class "Default")
      (node (ref "RPI1") (pin "7") (pinfunction "GPIO4_7") (pintype "bidirectional"))
    )
    (net (code "117") (name "unconnected-(RPI1-GPIO17-Pad11)") (class "Default")
      (node (ref "RPI1") (pin "11") (pinfunction "GPIO17_11") (pintype "bidirectional"))
    )
    (net (code "118") (name "unconnected-(U66-DCO-Pad6)") (class "Default")
      (node (ref "U66") (pin "6") (pinfunction "DCO_6") (pintype "unspecified"))
    )
    (net (code "119") (name "unconnected-(U66-DIR-Pad8)") (class "Default")
      (node (ref "U66") (pin "8") (pinfunction "DIR_8") (pintype "unspecified"))
    )
    (net (code "120") (name "unconnected-(U66-MS1-Pad2)") (class "Default")
      (node (ref "U66") (pin "2") (pinfunction "MS1_2") (pintype "unspecified"))
    )
    (net (code "121") (name "unconnected-(U66-MS2-Pad3)") (class "Default")
      (node (ref "U66") (pin "3") (pinfunction "MS2_3") (pintype "unspecified"))
    )
    (net (code "122") (name "unconnected-(U66-STEP-Pad7)") (class "Default")
      (node (ref "U66") (pin "7") (pinfunction "STEP_7") (pintype "unspecified"))
    )
    (net (code "123") (name "unconnected-(U67-DCO-Pad6)") (class "Default")
      (node (ref "U67") (pin "6") (pinfunction "DCO_6") (pintype "unspecified"))
    )
    (net (code "124") (name "unconnected-(U67-DIR-Pad8)") (class "Default")
      (node (ref "U67") (pin "8") (pinfunction "DIR_8") (pintype "unspecified"))
    )
    (net (code "125") (name "unconnected-(U67-MS1-Pad2)") (class "Default")
      (node (ref "U67") (pin "2") (pinfunction "MS1_2") (pintype "unspecified"))
    )
    (net (code "126") (name "unconnected-(U67-MS2-Pad3)") (class "Default")
      (node (ref "U67") (pin "3") (pinfunction "MS2_3") (pintype "unspecified"))
    )
    (net (code "127") (name "unconnected-(U67-STEP-Pad7)") (class "Default")
      (node (ref "U67") (pin "7") (pinfunction "STEP_7") (pintype "unspecified"))
    )
  )
)
